# ECAM03.net
KiCad netlist of a schematic drawn in EAGLE
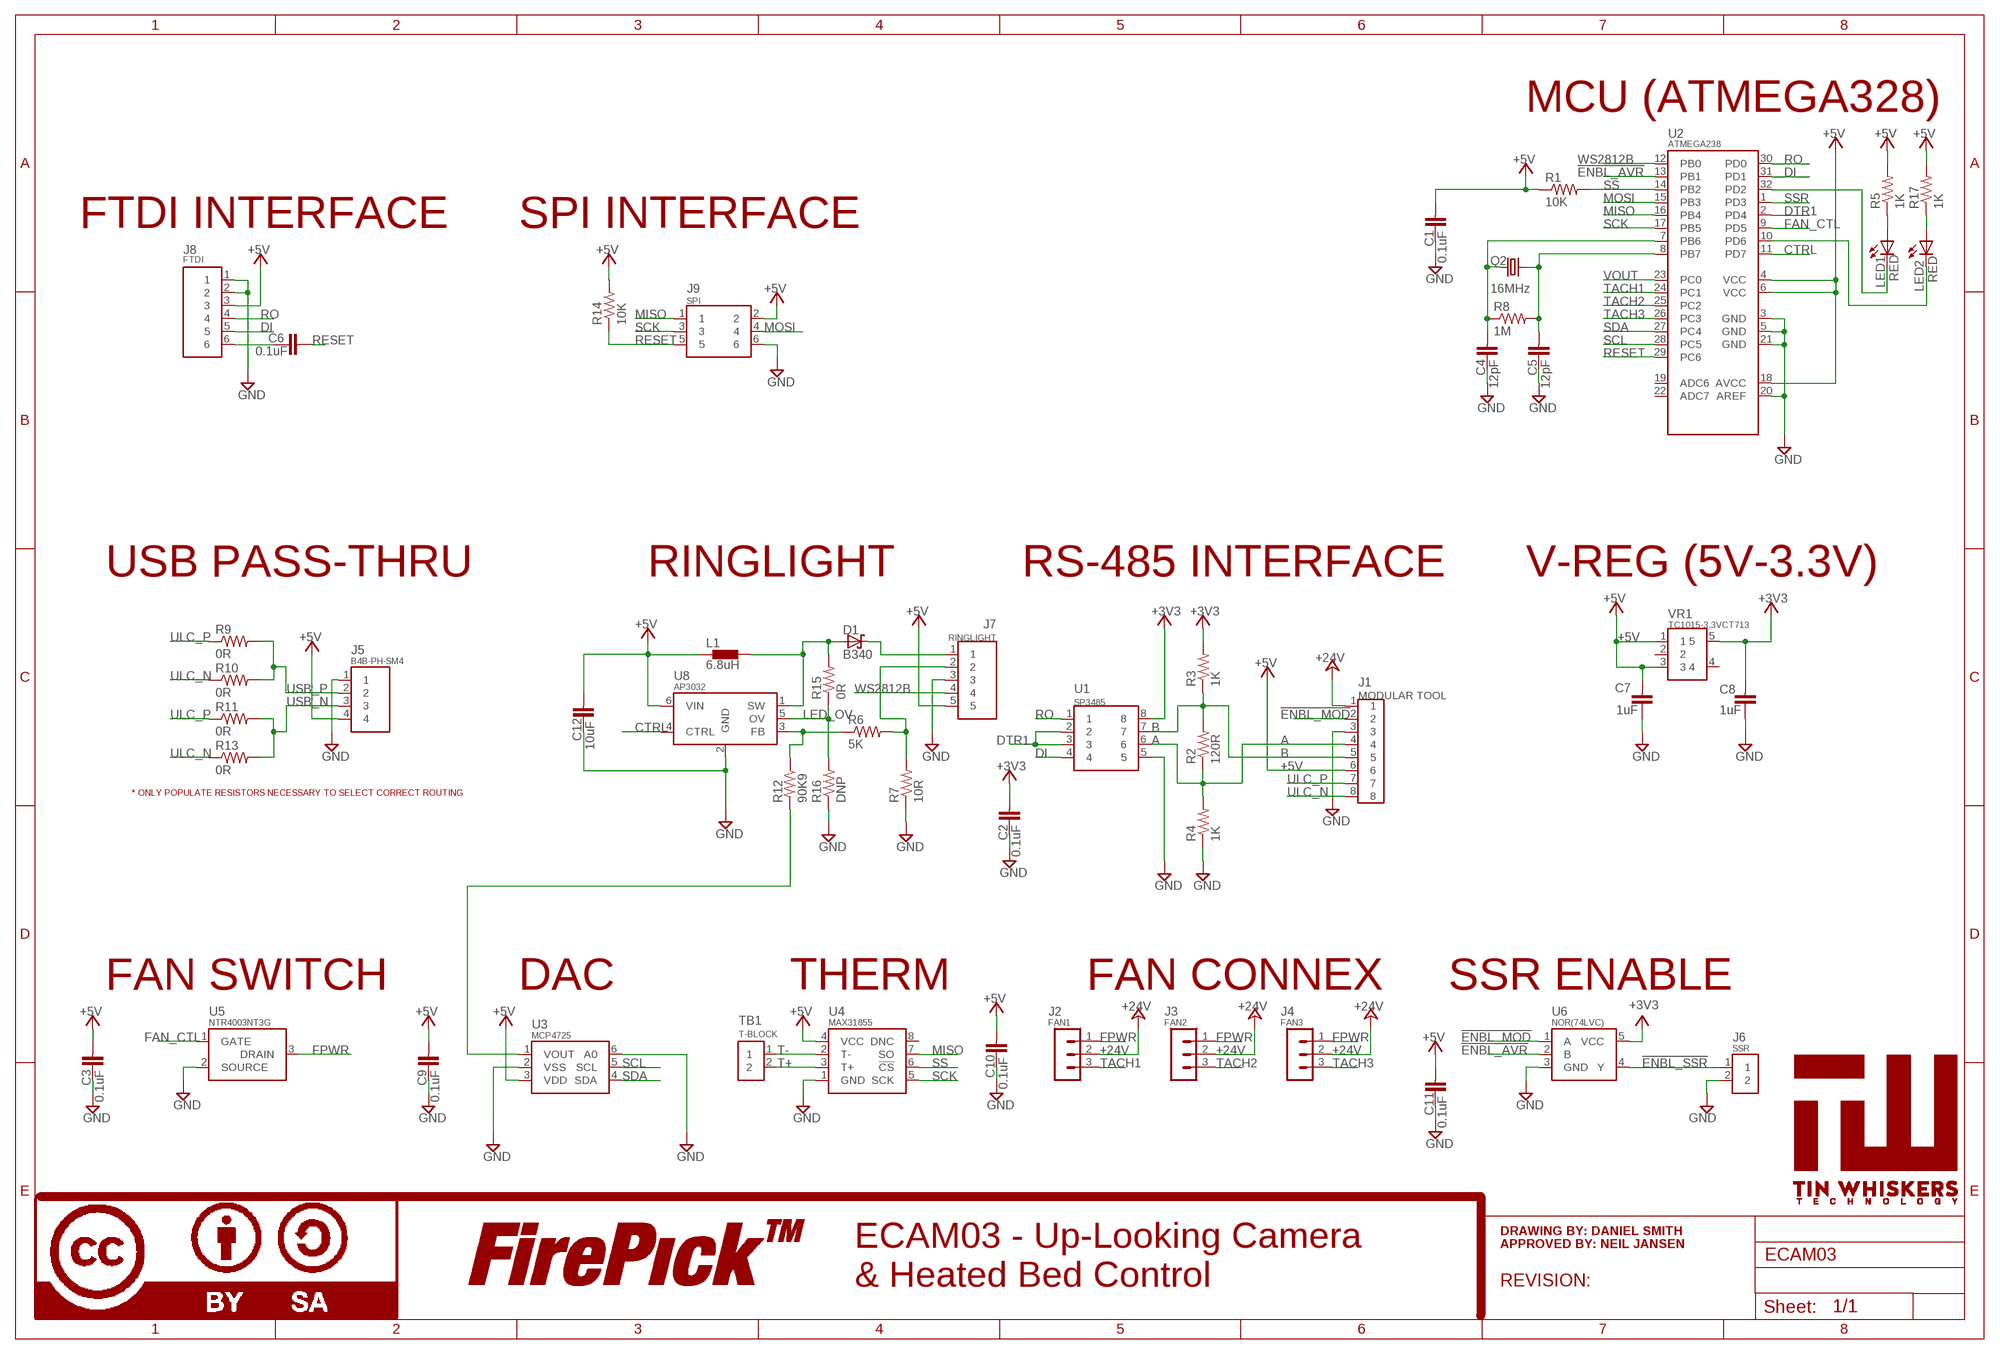
[diagram p0: schematic, sheet 1]

(export (version "E")
  (design (tool "Eeschema 10.0.6"))
  (components
    (comp (ref "C1")
      (value "0.1uF")
      (footprint "eagle-import:C0603")
      (libsource (lib "eagle-import") (part "CPL-CAP-X5R-0603-0.1UF-35V"))
    )
    (comp (ref "C2")
      (value "0.1uF")
      (footprint "eagle-import:C0603")
      (libsource (lib "eagle-import") (part "CPL-CAP-X5R-0603-0.1UF-35V"))
    )
    (comp (ref "C3")
      (value "0.1uF")
      (footprint "eagle-import:C0603")
      (libsource (lib "eagle-import") (part "CPL-CAP-X5R-0603-0.1UF-35V"))
    )
    (comp (ref "C4")
      (value "12pF")
      (footprint "eagle-import:C0603")
      (fields (field (name "PARTNO") "GRM1885C1H120FA01J"))
      (libsource (lib "eagle-import") (part "CPL-CAP-C0G-0603-12PF-50V"))
    )
    (comp (ref "C5")
      (value "12pF")
      (footprint "eagle-import:C0603")
      (fields (field (name "PARTNO") "GRM1885C1H120FA01J"))
      (libsource (lib "eagle-import") (part "CPL-CAP-C0G-0603-12PF-50V"))
    )
    (comp (ref "C6")
      (value "0.1uF")
      (footprint "eagle-import:C0603")
      (fields (field (name "PARTNO") "UMK107B7104KA-T"))
      (libsource (lib "eagle-import") (part "CPL-CAP-X7R-0603-100NF-50V"))
    )
    (comp (ref "C7")
      (value "1uF")
      (footprint "eagle-import:C0603")
      (fields (field (name "PARTNO") "UMK107AB7105KA-T"))
      (libsource (lib "eagle-import") (part "CPL-CAP-X5R-0603-1UF-50V"))
    )
    (comp (ref "C8")
      (value "1uF")
      (footprint "eagle-import:C0603")
      (fields (field (name "PARTNO") "UMK107AB7105KA-T"))
      (libsource (lib "eagle-import") (part "CPL-CAP-X5R-0603-1UF-50V"))
    )
    (comp (ref "C9")
      (value "0.1uF")
      (footprint "eagle-import:C0603")
      (libsource (lib "eagle-import") (part "CPL-CAP-X5R-0603-0.1UF-35V"))
    )
    (comp (ref "C10")
      (value "0.1uF")
      (footprint "eagle-import:C0603")
      (libsource (lib "eagle-import") (part "CPL-CAP-X5R-0603-0.1UF-35V"))
    )
    (comp (ref "C11")
      (value "0.1uF")
      (footprint "eagle-import:C0603")
      (libsource (lib "eagle-import") (part "CPL-CAP-X5R-0603-0.1UF-35V"))
    )
    (comp (ref "C12")
      (value "10uF")
      (footprint "eagle-import:C0603")
      (fields (field (name "PARTNO") "GRM188R61C106MA73D"))
      (libsource (lib "eagle-import") (part "CPL-CAP-X5R-0603-10UF-25V"))
    )
    (comp (ref "D1")
      (value "B340")
      (footprint "eagle-import:DIO-SMA")
      (fields (field (name "PARTNO") "B340A-13-F"))
      (libsource (lib "eagle-import") (part "CPL-DIO-B340-13-F-SMA"))
    )
    (comp (ref "J1")
      (value "MODULAR TOOL")
      (footprint "eagle-import:CONN-JST-PH-2.0MM-8P-SMT-RA")
      (fields (field (name "PARTNO") "S8B-PH-SM4-TB(LF)(SN)"))
      (libsource (lib "eagle-import") (part "CPL-CON-JST-2.0MM-8P-M-RA"))
    )
    (comp (ref "J2")
      (value "FAN1")
      (footprint "eagle-import:CONN-MOLEX-KK-3PIN")
      (fields (field (name "PARTNO") "22232031"))
      (libsource (lib "eagle-import") (part "CONN-RECT-3PINMOLEX-KK"))
    )
    (comp (ref "J3")
      (value "FAN2")
      (footprint "eagle-import:CONN-MOLEX-KK-3PIN")
      (fields (field (name "PARTNO") "22232031"))
      (libsource (lib "eagle-import") (part "CONN-RECT-3PINMOLEX-KK"))
    )
    (comp (ref "J4")
      (value "FAN3")
      (footprint "eagle-import:CONN-MOLEX-KK-3PIN")
      (fields (field (name "PARTNO") "22232031"))
      (libsource (lib "eagle-import") (part "CONN-RECT-3PINMOLEX-KK"))
    )
    (comp (ref "J5")
      (value "B4B-PH-SM4")
      (footprint "eagle-import:CON-JST-PH-2.0MM-4P-SMT-VRT")
      (fields (field (name "PARTNO") "B4B-PH-SM4-TB(LF)(SN)"))
      (libsource (lib "eagle-import") (part "CPL-CON-JST-2.0MM-4P-M-SMT-VRT"))
    )
    (comp (ref "J6")
      (value "SSR")
      (footprint "eagle-import:CON-HDR-2POS-MALE")
      (fields (field (name "PARTNO") "68000-102HLF"))
      (libsource (lib "eagle-import") (part "CPL-CON-HEADER-0.1IN-2P-M"))
    )
    (comp (ref "J7")
      (value "RINGLIGHT")
      (footprint "eagle-import:CON-JST-PH-2.0MM-5P-SMT-VRT")
      (fields (field (name "PARTNO") "B5B-PH-SM4-TB(LF)(SN)"))
      (libsource (lib "eagle-import") (part "CPL-CON-JST-2.0MM-5P-SMT-VRT"))
    )
    (comp (ref "J8")
      (value "FTDI")
      (footprint "eagle-import:CON-HDR-6POS-MALE")
      (fields (field (name "PARTNO") "S6B-PH-SM4-TB(LF)(SN)"))
      (libsource (lib "eagle-import") (part "CPL-CON-HEADER-0.1IN-6P-M"))
    )
    (comp (ref "J9")
      (value "SPI")
      (footprint "eagle-import:CON-HDR-2X3P")
      (fields (field (name "PARTNO") "67996-206HLF"))
      (libsource (lib "eagle-import") (part "CPL-CON-HEADER-0.1IN-2X3P-M"))
    )
    (comp (ref "L1")
      (value "6.8uH")
      (footprint "eagle-import:0603")
      (fields (field (name "PARTNO") "BRL1608T6R8M"))
      (libsource (lib "eagle-import") (part "CPL-IND-6.8UH-250MA"))
    )
    (comp (ref "LED1")
      (value "RED")
      (footprint "eagle-import:LED0603")
      (libsource (lib "eagle-import") (part "CPL-LED-0603-RED"))
    )
    (comp (ref "LED2")
      (value "RED")
      (footprint "eagle-import:LED0603")
      (libsource (lib "eagle-import") (part "CPL-LED-0603-RED"))
    )
    (comp (ref "LOGO1")
      (value "LOGO-CC-BY-SALARGE")
      (footprint "eagle-import:LOGO-CC-BY-SA")
      (libsource (lib "eagle-import") (part "LOGO-CC-BY-SALARGE"))
    )
    (comp (ref "LOGO2")
      (value "LOGO-FIREPICKLARGE")
      (footprint "eagle-import:LOGO-FIREPICK")
      (libsource (lib "eagle-import") (part "LOGO-FIREPICKLARGE"))
    )
    (comp (ref "Q2")
      (value "16MHz")
      (footprint "eagle-import:HC-49_U-S")
      (fields (field (name "PARTNO") "HCM4916000000ABJT"))
      (libsource (lib "eagle-import") (part "CPL-OSC-CRY-16MHZ-18PF"))
    )
    (comp (ref "R1")
      (value "10K")
      (footprint "eagle-import:R0603")
      (fields (field (name "PARTNO") "RC0603FR-0710KL"))
      (libsource (lib "eagle-import") (part "CPL-RES-0603-10K-0.1W"))
    )
    (comp (ref "R2")
      (value "120R")
      (footprint "eagle-import:R0603")
      (fields (field (name "PARTNO") "RC0603FR-07120RL"))
      (libsource (lib "eagle-import") (part "CPL-RES-0603-120-0.1W"))
    )
    (comp (ref "R3")
      (value "1K")
      (footprint "eagle-import:R0603")
      (fields (field (name "PARTNO") "RC0603FR-071KL"))
      (libsource (lib "eagle-import") (part "CPL-RES-0603-1K-0.1W"))
    )
    (comp (ref "R4")
      (value "1K")
      (footprint "eagle-import:R0603")
      (fields (field (name "PARTNO") "RC0603FR-071KL"))
      (libsource (lib "eagle-import") (part "CPL-RES-0603-1K-0.1W"))
    )
    (comp (ref "R5")
      (value "1K")
      (footprint "eagle-import:R0603")
      (libsource (lib "eagle-import") (part "CPL-RES-0603-1K-0.1W"))
    )
    (comp (ref "R6")
      (value "5K")
      (footprint "eagle-import:R0603")
      (fields (field (name "PARTNO") "RC0603FR-074K99L"))
      (libsource (lib "eagle-import") (part "CPL-RES-0603-5K-0.1W"))
    )
    (comp (ref "R7")
      (value "10R")
      (footprint "eagle-import:R1206")
      (fields (field (name "PARTNO") "RC1206FR-0710RL"))
      (libsource (lib "eagle-import") (part "CPL-RES-1206-10-0.25W1206"))
    )
    (comp (ref "R8")
      (value "1M")
      (footprint "eagle-import:R0603")
      (fields (field (name "PARTNO") "RC0603FR-071ML"))
      (libsource (lib "eagle-import") (part "CPL-RES-0603-1M-0.1W"))
    )
    (comp (ref "R9")
      (value "0R")
      (footprint "eagle-import:R0603")
      (fields (field (name "PARTNO") "RC0603JR-070RL"))
      (libsource (lib "eagle-import") (part "CPL-RES-0603-0-0.1W"))
    )
    (comp (ref "R10")
      (value "0R")
      (footprint "eagle-import:R0603")
      (fields (field (name "PARTNO") "RC0603JR-070RL"))
      (libsource (lib "eagle-import") (part "CPL-RES-0603-0-0.1W"))
    )
    (comp (ref "R11")
      (value "0R")
      (footprint "eagle-import:R0603")
      (fields (field (name "PARTNO") "RC0603JR-070RL"))
      (libsource (lib "eagle-import") (part "CPL-RES-0603-0-0.1W"))
    )
    (comp (ref "R12")
      (value "90K9")
      (footprint "eagle-import:R0603")
      (fields (field (name "PARTNO") "RC0603FR-0790K9L"))
      (libsource (lib "eagle-import") (part "CPL-RES-0603-90K-0.1W"))
    )
    (comp (ref "R13")
      (value "0R")
      (footprint "eagle-import:R0603")
      (fields (field (name "PARTNO") "RC0603JR-070RL"))
      (libsource (lib "eagle-import") (part "CPL-RES-0603-0-0.1W"))
    )
    (comp (ref "R14")
      (value "10K")
      (footprint "eagle-import:R0603")
      (fields (field (name "PARTNO") "RC0603FR-0710KL"))
      (libsource (lib "eagle-import") (part "CPL-RES-0603-10K-0.1W"))
    )
    (comp (ref "R15")
      (value "0R")
      (footprint "eagle-import:R0603")
      (fields (field (name "PARTNO") "RC0603JR-070RL"))
      (libsource (lib "eagle-import") (part "CPL-RES-0603-0-0.1W"))
    )
    (comp (ref "R16")
      (value "DNP")
      (footprint "eagle-import:R0603")
      (fields (field (name "PARTNO") "RC0603JR-070RL"))
      (libsource (lib "eagle-import") (part "CPL-RES-0603-0-0.1W"))
    )
    (comp (ref "R17")
      (value "1K")
      (footprint "eagle-import:R0603")
      (libsource (lib "eagle-import") (part "CPL-RES-0603-1K-0.1W"))
    )
    (comp (ref "TB1")
      (value "T-BLOCK")
      (footprint "eagle-import:TBLOCK-2-5MM-OSTTH020160")
      (fields (field (name "PARTNO") "OSTTH020160"))
      (libsource (lib "eagle-import") (part "CPL-TBLK-SCR-2CKT-5.0MM-OST"))
    )
    (comp (ref "U$1")
      (value "TIN-WHISKERSTSTOP")
      (footprint "eagle-import:TIN-WHISKERS-TSTOP")
      (libsource (lib "eagle-import") (part "TIN-WHISKERSTSTOP"))
    )
    (comp (ref "U1")
      (value "SP3485")
      (footprint "eagle-import:SOICN-8")
      (libsource (lib "eagle-import") (part "SP3485"))
    )
    (comp (ref "U2")
      (value "ATMEGA238")
      (footprint "eagle-import:32-TQF(ATMEGA)")
      (fields (field (name "PARTNO") "ATMEGA328-AUR"))
      (libsource (lib "eagle-import") (part "CPL-MCU-ATMEL-AT328-32TQFP"))
    )
    (comp (ref "U3")
      (value "MCP4725")
      (footprint "eagle-import:SOT-23-6")
      (fields (field (name "PARTNO") "MCP4725A0T-E/CH"))
      (libsource (lib "eagle-import") (part "CPL-DAC-12BIT-SOT23"))
    )
    (comp (ref "U4")
      (value "MAX31855")
      (footprint "eagle-import:SOICN-8")
      (fields (field (name "PARTNO") "MAX31855KASA+"))
      (libsource (lib "eagle-import") (part "CPL-THRM-MAX31855"))
    )
    (comp (ref "U5")
      (value "NTR4003NT3G")
      (footprint "eagle-import:SOT-23-3")
      (libsource (lib "eagle-import") (part "CPL-MOSFET-NCH-SOT23NTR4003N"))
    )
    (comp (ref "U6")
      (value "NOR(74LVC)")
      (footprint "eagle-import:SOT-23-5")
      (fields (field (name "PARTNO") "SN74LVC1G02DBVR"))
      (libsource (lib "eagle-import") (part "CPL-IC-LOGIC-NOR-1CH-74LVC"))
    )
    (comp (ref "U8")
      (value "AP3032")
      (footprint "eagle-import:SOT-23-6")
      (fields (field (name "PARTNO") "AP3032KTR-G1"))
      (libsource (lib "eagle-import") (part "CPL-LED-DRIVER-WHT-AP3032"))
    )
    (comp (ref "VR1")
      (value "TC1015-3.3VCT713")
      (footprint "eagle-import:SOT-23-5")
      (libsource (lib "eagle-import") (part "CPL-REG-LIN-3.3V-0.1A"))
    )
  )
  (nets
    (net (code "1") (name "+3V3") (class "Default")
      (node (ref "C2") (pin "2") (pinfunction "2_2") (pintype "passive"))
      (node (ref "C8") (pin "2") (pinfunction "2_2") (pintype "passive"))
      (node (ref "R3") (pin "2") (pinfunction "2_2") (pintype "passive"))
      (node (ref "U1") (pin "8") (pinfunction "8_8") (pintype "bidirectional"))
      (node (ref "U6") (pin "5") (pinfunction "VCC_5") (pintype "bidirectional"))
      (node (ref "VR1") (pin "5") (pinfunction "5_5") (pintype "passive"))
    )
    (net (code "2") (name "+5V") (class "Default")
      (node (ref "C1") (pin "2") (pinfunction "2_2") (pintype "passive"))
      (node (ref "C10") (pin "2") (pinfunction "2_2") (pintype "passive"))
      (node (ref "C11") (pin "2") (pinfunction "2_2") (pintype "passive"))
      (node (ref "C12") (pin "2") (pinfunction "2_2") (pintype "passive"))
      (node (ref "C3") (pin "2") (pinfunction "2_2") (pintype "passive"))
      (node (ref "C7") (pin "2") (pinfunction "2_2") (pintype "passive"))
      (node (ref "C9") (pin "2") (pinfunction "2_2") (pintype "passive"))
      (node (ref "J1") (pin "6") (pinfunction "6_6") (pintype "passive"))
      (node (ref "J5") (pin "4") (pinfunction "4_4") (pintype "passive"))
      (node (ref "J7") (pin "5") (pinfunction "5_5") (pintype "bidirectional"))
      (node (ref "J8") (pin "3") (pinfunction "3_3") (pintype "bidirectional"))
      (node (ref "J9") (pin "2") (pinfunction "2_2") (pintype "passive"))
      (node (ref "L1") (pin "1") (pinfunction "1_1") (pintype "passive"))
      (node (ref "R1") (pin "1") (pinfunction "1_1") (pintype "passive"))
      (node (ref "R14") (pin "2") (pinfunction "2_2") (pintype "passive"))
      (node (ref "R17") (pin "2") (pinfunction "2_2") (pintype "passive"))
      (node (ref "R5") (pin "2") (pinfunction "2_2") (pintype "passive"))
      (node (ref "U2") (pin "18") (pinfunction "AVCC_18") (pintype "bidirectional"))
      (node (ref "U2") (pin "4") (pinfunction "VCC_4") (pintype "bidirectional"))
      (node (ref "U2") (pin "6") (pinfunction "VCC_6") (pintype "bidirectional"))
      (node (ref "U3") (pin "3") (pinfunction "VDD_3") (pintype "bidirectional"))
      (node (ref "U4") (pin "4") (pinfunction "VCC_4") (pintype "bidirectional"))
      (node (ref "U8") (pin "6") (pinfunction "VIN_6") (pintype "bidirectional"))
      (node (ref "VR1") (pin "1") (pinfunction "1_1") (pintype "passive"))
      (node (ref "VR1") (pin "3") (pinfunction "3_3") (pintype "passive"))
    )
    (net (code "3") (name "+24V") (class "Default")
      (node (ref "J1") (pin "1") (pinfunction "1_1") (pintype "passive"))
      (node (ref "J2") (pin "2") (pinfunction "2_2") (pintype "passive"))
      (node (ref "J3") (pin "2") (pinfunction "2_2") (pintype "passive"))
      (node (ref "J4") (pin "2") (pinfunction "2_2") (pintype "passive"))
    )
    (net (code "4") (name "/A") (class "Default")
      (node (ref "J1") (pin "4") (pinfunction "4_4") (pintype "passive"))
      (node (ref "R2") (pin "1") (pinfunction "1_1") (pintype "passive"))
      (node (ref "R4") (pin "2") (pinfunction "2_2") (pintype "passive"))
      (node (ref "U1") (pin "6") (pinfunction "6_6") (pintype "bidirectional"))
    )
    (net (code "5") (name "/B") (class "Default")
      (node (ref "J1") (pin "5") (pinfunction "5_5") (pintype "passive"))
      (node (ref "R2") (pin "2") (pinfunction "2_2") (pintype "passive"))
      (node (ref "R3") (pin "1") (pinfunction "1_1") (pintype "passive"))
      (node (ref "U1") (pin "7") (pinfunction "7_7") (pintype "bidirectional"))
    )
    (net (code "6") (name "/CTRL") (class "Default")
      (node (ref "U2") (pin "11") (pinfunction "PD7_11") (pintype "bidirectional"))
      (node (ref "U8") (pin "4") (pinfunction "CTRL_4") (pintype "bidirectional"))
    )
    (net (code "7") (name "/DI") (class "Default")
      (node (ref "J8") (pin "5") (pinfunction "5_5") (pintype "bidirectional"))
      (node (ref "U1") (pin "4") (pinfunction "4_4") (pintype "bidirectional"))
      (node (ref "U2") (pin "31") (pinfunction "PD1_31") (pintype "bidirectional"))
    )
    (net (code "8") (name "/DTR1") (class "Default")
      (node (ref "U1") (pin "2") (pinfunction "2_2") (pintype "bidirectional"))
      (node (ref "U1") (pin "3") (pinfunction "3_3") (pintype "bidirectional"))
      (node (ref "U2") (pin "2") (pinfunction "PD4_2") (pintype "bidirectional"))
    )
    (net (code "9") (name "/FAN_CTL") (class "Default")
      (node (ref "U2") (pin "9") (pinfunction "PD5_9") (pintype "bidirectional"))
      (node (ref "U5") (pin "1") (pinfunction "GATE_1") (pintype "bidirectional"))
    )
    (net (code "10") (name "/FPWR") (class "Default")
      (node (ref "J2") (pin "1") (pinfunction "1_1") (pintype "passive"))
      (node (ref "J3") (pin "1") (pinfunction "1_1") (pintype "passive"))
      (node (ref "J4") (pin "1") (pinfunction "1_1") (pintype "passive"))
      (node (ref "U5") (pin "3") (pinfunction "DRAIN_3") (pintype "bidirectional"))
    )
    (net (code "11") (name "/LED_OV") (class "Default")
      (node (ref "R15") (pin "1") (pinfunction "1_1") (pintype "passive"))
      (node (ref "R16") (pin "2") (pinfunction "2_2") (pintype "passive"))
      (node (ref "U8") (pin "5") (pinfunction "OV_5") (pintype "bidirectional"))
    )
    (net (code "12") (name "/MISO") (class "Default")
      (node (ref "J9") (pin "1") (pinfunction "1_1") (pintype "passive"))
      (node (ref "U2") (pin "16") (pinfunction "PB4_16") (pintype "bidirectional"))
      (node (ref "U4") (pin "7") (pinfunction "SO_7") (pintype "bidirectional"))
    )
    (net (code "13") (name "/MOSI") (class "Default")
      (node (ref "J9") (pin "4") (pinfunction "4_4") (pintype "passive"))
      (node (ref "U2") (pin "15") (pinfunction "PB3_15") (pintype "bidirectional"))
    )
    (net (code "14") (name "/RESET") (class "Default")
      (node (ref "C6") (pin "2") (pinfunction "2_2") (pintype "passive"))
      (node (ref "J9") (pin "5") (pinfunction "5_5") (pintype "passive"))
      (node (ref "R14") (pin "1") (pinfunction "1_1") (pintype "passive"))
      (node (ref "U2") (pin "29") (pinfunction "PC6_29") (pintype "bidirectional"))
    )
    (net (code "15") (name "/RO") (class "Default")
      (node (ref "J8") (pin "4") (pinfunction "4_4") (pintype "bidirectional"))
      (node (ref "U1") (pin "1") (pinfunction "1_1") (pintype "bidirectional"))
      (node (ref "U2") (pin "30") (pinfunction "PD0_30") (pintype "bidirectional"))
    )
    (net (code "16") (name "/SCK") (class "Default")
      (node (ref "J9") (pin "3") (pinfunction "3_3") (pintype "passive"))
      (node (ref "U2") (pin "17") (pinfunction "PB5_17") (pintype "bidirectional"))
      (node (ref "U4") (pin "5") (pinfunction "SCK_5") (pintype "bidirectional"))
    )
    (net (code "17") (name "/SCL") (class "Default")
      (node (ref "U2") (pin "28") (pinfunction "PC5_28") (pintype "bidirectional"))
      (node (ref "U3") (pin "5") (pinfunction "SCL_5") (pintype "bidirectional"))
    )
    (net (code "18") (name "/SDA") (class "Default")
      (node (ref "U2") (pin "27") (pinfunction "PC4_27") (pintype "bidirectional"))
      (node (ref "U3") (pin "4") (pinfunction "SDA_4") (pintype "bidirectional"))
    )
    (net (code "19") (name "/SS") (class "Default")
      (node (ref "R1") (pin "2") (pinfunction "2_2") (pintype "passive"))
      (node (ref "U2") (pin "14") (pinfunction "PB2_14") (pintype "bidirectional"))
      (node (ref "U4") (pin "6") (pinfunction "~{CS}_6") (pintype "bidirectional"))
    )
    (net (code "20") (name "/SSR") (class "Default")
      (node (ref "U2") (pin "1") (pinfunction "PD3_1") (pintype "bidirectional"))
    )
    (net (code "21") (name "/T+") (class "Default")
      (node (ref "TB1") (pin "2") (pinfunction "2_2") (pintype "passive"))
      (node (ref "U4") (pin "3") (pinfunction "T+_3") (pintype "bidirectional"))
    )
    (net (code "22") (name "/T-") (class "Default")
      (node (ref "TB1") (pin "1") (pinfunction "1_1") (pintype "passive"))
      (node (ref "U4") (pin "2") (pinfunction "T-_2") (pintype "bidirectional"))
    )
    (net (code "23") (name "/TACH1") (class "Default")
      (node (ref "J2") (pin "3") (pinfunction "3_3") (pintype "passive"))
      (node (ref "U2") (pin "24") (pinfunction "PC1_24") (pintype "bidirectional"))
    )
    (net (code "24") (name "/TACH2") (class "Default")
      (node (ref "J3") (pin "3") (pinfunction "3_3") (pintype "passive"))
      (node (ref "U2") (pin "25") (pinfunction "PC2_25") (pintype "bidirectional"))
    )
    (net (code "25") (name "/TACH3") (class "Default")
      (node (ref "J4") (pin "3") (pinfunction "3_3") (pintype "passive"))
      (node (ref "U2") (pin "26") (pinfunction "PC3_26") (pintype "bidirectional"))
    )
    (net (code "26") (name "/ULC_N") (class "Default")
      (node (ref "J1") (pin "8") (pinfunction "8_8") (pintype "passive"))
      (node (ref "R10") (pin "1") (pinfunction "1_1") (pintype "passive"))
      (node (ref "R13") (pin "1") (pinfunction "1_1") (pintype "passive"))
    )
    (net (code "27") (name "/ULC_P") (class "Default")
      (node (ref "J1") (pin "7") (pinfunction "7_7") (pintype "passive"))
      (node (ref "R11") (pin "1") (pinfunction "1_1") (pintype "passive"))
      (node (ref "R9") (pin "1") (pinfunction "1_1") (pintype "passive"))
    )
    (net (code "28") (name "/USB_N") (class "Default")
      (node (ref "J5") (pin "3") (pinfunction "3_3") (pintype "passive"))
      (node (ref "R11") (pin "2") (pinfunction "2_2") (pintype "passive"))
      (node (ref "R13") (pin "2") (pinfunction "2_2") (pintype "passive"))
    )
    (net (code "29") (name "/USB_P") (class "Default")
      (node (ref "J5") (pin "2") (pinfunction "2_2") (pintype "passive"))
      (node (ref "R10") (pin "2") (pinfunction "2_2") (pintype "passive"))
      (node (ref "R9") (pin "2") (pinfunction "2_2") (pintype "passive"))
    )
    (net (code "30") (name "/VOUT") (class "Default")
      (node (ref "U2") (pin "23") (pinfunction "PC0_23") (pintype "bidirectional"))
    )
    (net (code "31") (name "/WS2812B") (class "Default")
      (node (ref "J7") (pin "4") (pinfunction "4_4") (pintype "bidirectional"))
      (node (ref "U2") (pin "12") (pinfunction "PB0_12") (pintype "bidirectional"))
    )
    (net (code "32") (name "/~{ENBL_AVR}") (class "Default")
      (node (ref "U2") (pin "13") (pinfunction "PB1_13") (pintype "bidirectional"))
      (node (ref "U6") (pin "2") (pinfunction "B_2") (pintype "bidirectional"))
    )
    (net (code "33") (name "/~{ENBL_MOD}") (class "Default")
      (node (ref "J1") (pin "2") (pinfunction "2_2") (pintype "passive"))
      (node (ref "U6") (pin "1") (pinfunction "A_1") (pintype "bidirectional"))
    )
    (net (code "34") (name "/~{ENBL_SSR}") (class "Default")
      (node (ref "J6") (pin "1") (pinfunction "1_1") (pintype "passive"))
      (node (ref "U6") (pin "4") (pinfunction "Y_4") (pintype "bidirectional"))
    )
    (net (code "35") (name "GND") (class "Default")
      (node (ref "C1") (pin "1") (pinfunction "1_1") (pintype "passive"))
      (node (ref "C10") (pin "1") (pinfunction "1_1") (pintype "passive"))
      (node (ref "C11") (pin "1") (pinfunction "1_1") (pintype "passive"))
      (node (ref "C12") (pin "1") (pinfunction "1_1") (pintype "passive"))
      (node (ref "C2") (pin "1") (pinfunction "1_1") (pintype "passive"))
      (node (ref "C3") (pin "1") (pinfunction "1_1") (pintype "passive"))
      (node (ref "C4") (pin "1") (pinfunction "1_1") (pintype "passive"))
      (node (ref "C5") (pin "1") (pinfunction "1_1") (pintype "passive"))
      (node (ref "C7") (pin "1") (pinfunction "1_1") (pintype "passive"))
      (node (ref "C8") (pin "1") (pinfunction "1_1") (pintype "passive"))
      (node (ref "C9") (pin "1") (pinfunction "1_1") (pintype "passive"))
      (node (ref "J1") (pin "3") (pinfunction "3_3") (pintype "passive"))
      (node (ref "J5") (pin "1") (pinfunction "1_1") (pintype "passive"))
      (node (ref "J6") (pin "2") (pinfunction "2_2") (pintype "passive"))
      (node (ref "J7") (pin "3") (pinfunction "3_3") (pintype "bidirectional"))
      (node (ref "J8") (pin "1") (pinfunction "1_1") (pintype "bidirectional"))
      (node (ref "J8") (pin "2") (pinfunction "2_2") (pintype "bidirectional"))
      (node (ref "J9") (pin "6") (pinfunction "6_6") (pintype "passive"))
      (node (ref "R16") (pin "1") (pinfunction "1_1") (pintype "passive"))
      (node (ref "R4") (pin "1") (pinfunction "1_1") (pintype "passive"))
      (node (ref "R7") (pin "1") (pinfunction "1_1") (pintype "passive"))
      (node (ref "U1") (pin "5") (pinfunction "5_5") (pintype "bidirectional"))
      (node (ref "U2") (pin "20") (pinfunction "AREF_20") (pintype "bidirectional"))
      (node (ref "U2") (pin "21") (pinfunction "GND_21") (pintype "bidirectional"))
      (node (ref "U2") (pin "3") (pinfunction "GND_3") (pintype "bidirectional"))
      (node (ref "U2") (pin "5") (pinfunction "GND_5") (pintype "bidirectional"))
      (node (ref "U3") (pin "2") (pinfunction "VSS_2") (pintype "bidirectional"))
      (node (ref "U3") (pin "6") (pinfunction "A0_6") (pintype "bidirectional"))
      (node (ref "U4") (pin "1") (pinfunction "GND_1") (pintype "bidirectional"))
      (node (ref "U5") (pin "2") (pinfunction "SOURCE_2") (pintype "bidirectional"))
      (node (ref "U6") (pin "3") (pinfunction "GND_3") (pintype "bidirectional"))
      (node (ref "U8") (pin "2") (pinfunction "GND_2") (pintype "bidirectional"))
    )
    (net (code "36") (name "Net-(C6-Pad1)") (class "Default")
      (node (ref "C6") (pin "1") (pinfunction "1_1") (pintype "passive"))
      (node (ref "J8") (pin "6") (pinfunction "6_6") (pintype "bidirectional"))
    )
    (net (code "37") (name "Net-(D1-A)") (class "Default")
      (node (ref "D1") (pin "POS") (pinfunction "A_POS") (pintype "passive"))
      (node (ref "L1") (pin "2") (pinfunction "2_2") (pintype "passive"))
      (node (ref "R15") (pin "2") (pinfunction "2_2") (pintype "passive"))
      (node (ref "U8") (pin "1") (pinfunction "SW_1") (pintype "bidirectional"))
    )
    (net (code "38") (name "Net-(D1-C)") (class "Default")
      (node (ref "D1") (pin "NEG") (pinfunction "C_NEG") (pintype "passive"))
      (node (ref "J7") (pin "1") (pinfunction "1_1") (pintype "bidirectional"))
    )
    (net (code "39") (name "Net-(J7-Pad2)") (class "Default")
      (node (ref "J7") (pin "2") (pinfunction "2_2") (pintype "bidirectional"))
      (node (ref "R6") (pin "2") (pinfunction "2_2") (pintype "passive"))
      (node (ref "R7") (pin "2") (pinfunction "2_2") (pintype "passive"))
    )
    (net (code "40") (name "Net-(LED1-PadA)") (class "Default")
      (node (ref "LED1") (pin "A") (pinfunction "A_A") (pintype "passive"))
      (node (ref "R5") (pin "1") (pinfunction "1_1") (pintype "passive"))
    )
    (net (code "41") (name "Net-(LED2-PadA)") (class "Default")
      (node (ref "LED2") (pin "A") (pinfunction "A_A") (pintype "passive"))
      (node (ref "R17") (pin "1") (pinfunction "1_1") (pintype "passive"))
    )
    (net (code "42") (name "Net-(U2-PB6)") (class "Default")
      (node (ref "C4") (pin "2") (pinfunction "2_2") (pintype "passive"))
      (node (ref "Q2") (pin "1") (pinfunction "1_1") (pintype "passive"))
      (node (ref "R8") (pin "1") (pinfunction "1_1") (pintype "passive"))
      (node (ref "U2") (pin "7") (pinfunction "PB6_7") (pintype "bidirectional"))
    )
    (net (code "43") (name "Net-(U2-PB7)") (class "Default")
      (node (ref "C5") (pin "2") (pinfunction "2_2") (pintype "passive"))
      (node (ref "Q2") (pin "2") (pinfunction "2_2") (pintype "passive"))
      (node (ref "R8") (pin "2") (pinfunction "2_2") (pintype "passive"))
      (node (ref "U2") (pin "8") (pinfunction "PB7_8") (pintype "bidirectional"))
    )
    (net (code "44") (name "Net-(U2-PD2)") (class "Default")
      (node (ref "LED1") (pin "C") (pinfunction "C_C") (pintype "passive"))
      (node (ref "U2") (pin "32") (pinfunction "PD2_32") (pintype "bidirectional"))
    )
    (net (code "45") (name "Net-(U2-PD6)") (class "Default")
      (node (ref "LED2") (pin "C") (pinfunction "C_C") (pintype "passive"))
      (node (ref "U2") (pin "10") (pinfunction "PD6_10") (pintype "bidirectional"))
    )
    (net (code "46") (name "Net-(U3-VOUT)") (class "Default")
      (node (ref "R12") (pin "2") (pinfunction "2_2") (pintype "passive"))
      (node (ref "U3") (pin "1") (pinfunction "VOUT_1") (pintype "bidirectional"))
    )
    (net (code "47") (name "Net-(U8-FB)") (class "Default")
      (node (ref "R12") (pin "1") (pinfunction "1_1") (pintype "passive"))
      (node (ref "R6") (pin "1") (pinfunction "1_1") (pintype "passive"))
      (node (ref "U8") (pin "3") (pinfunction "FB_3") (pintype "bidirectional"))
    )
    (net (code "48") (name "unconnected-(U2-ADC6-Pad19)") (class "Default")
      (node (ref "U2") (pin "19") (pinfunction "ADC6_19") (pintype "bidirectional"))
    )
    (net (code "49") (name "unconnected-(U2-ADC7-Pad22)") (class "Default")
      (node (ref "U2") (pin "22") (pinfunction "ADC7_22") (pintype "bidirectional"))
    )
    (net (code "50") (name "unconnected-(U4-DNC-Pad8)") (class "Default")
      (node (ref "U4") (pin "8") (pinfunction "DNC_8") (pintype "bidirectional"))
    )
    (net (code "51") (name "unconnected-(VR1-Pad2)") (class "Default")
      (node (ref "VR1") (pin "2") (pinfunction "2_2") (pintype "passive"))
    )
    (net (code "52") (name "unconnected-(VR1-Pad4)") (class "Default")
      (node (ref "VR1") (pin "4") (pinfunction "4_4") (pintype "passive"))
    )
  )
)
